# MEGA2560_Rev3e.net
KiCad netlist of a schematic drawn in EAGLE
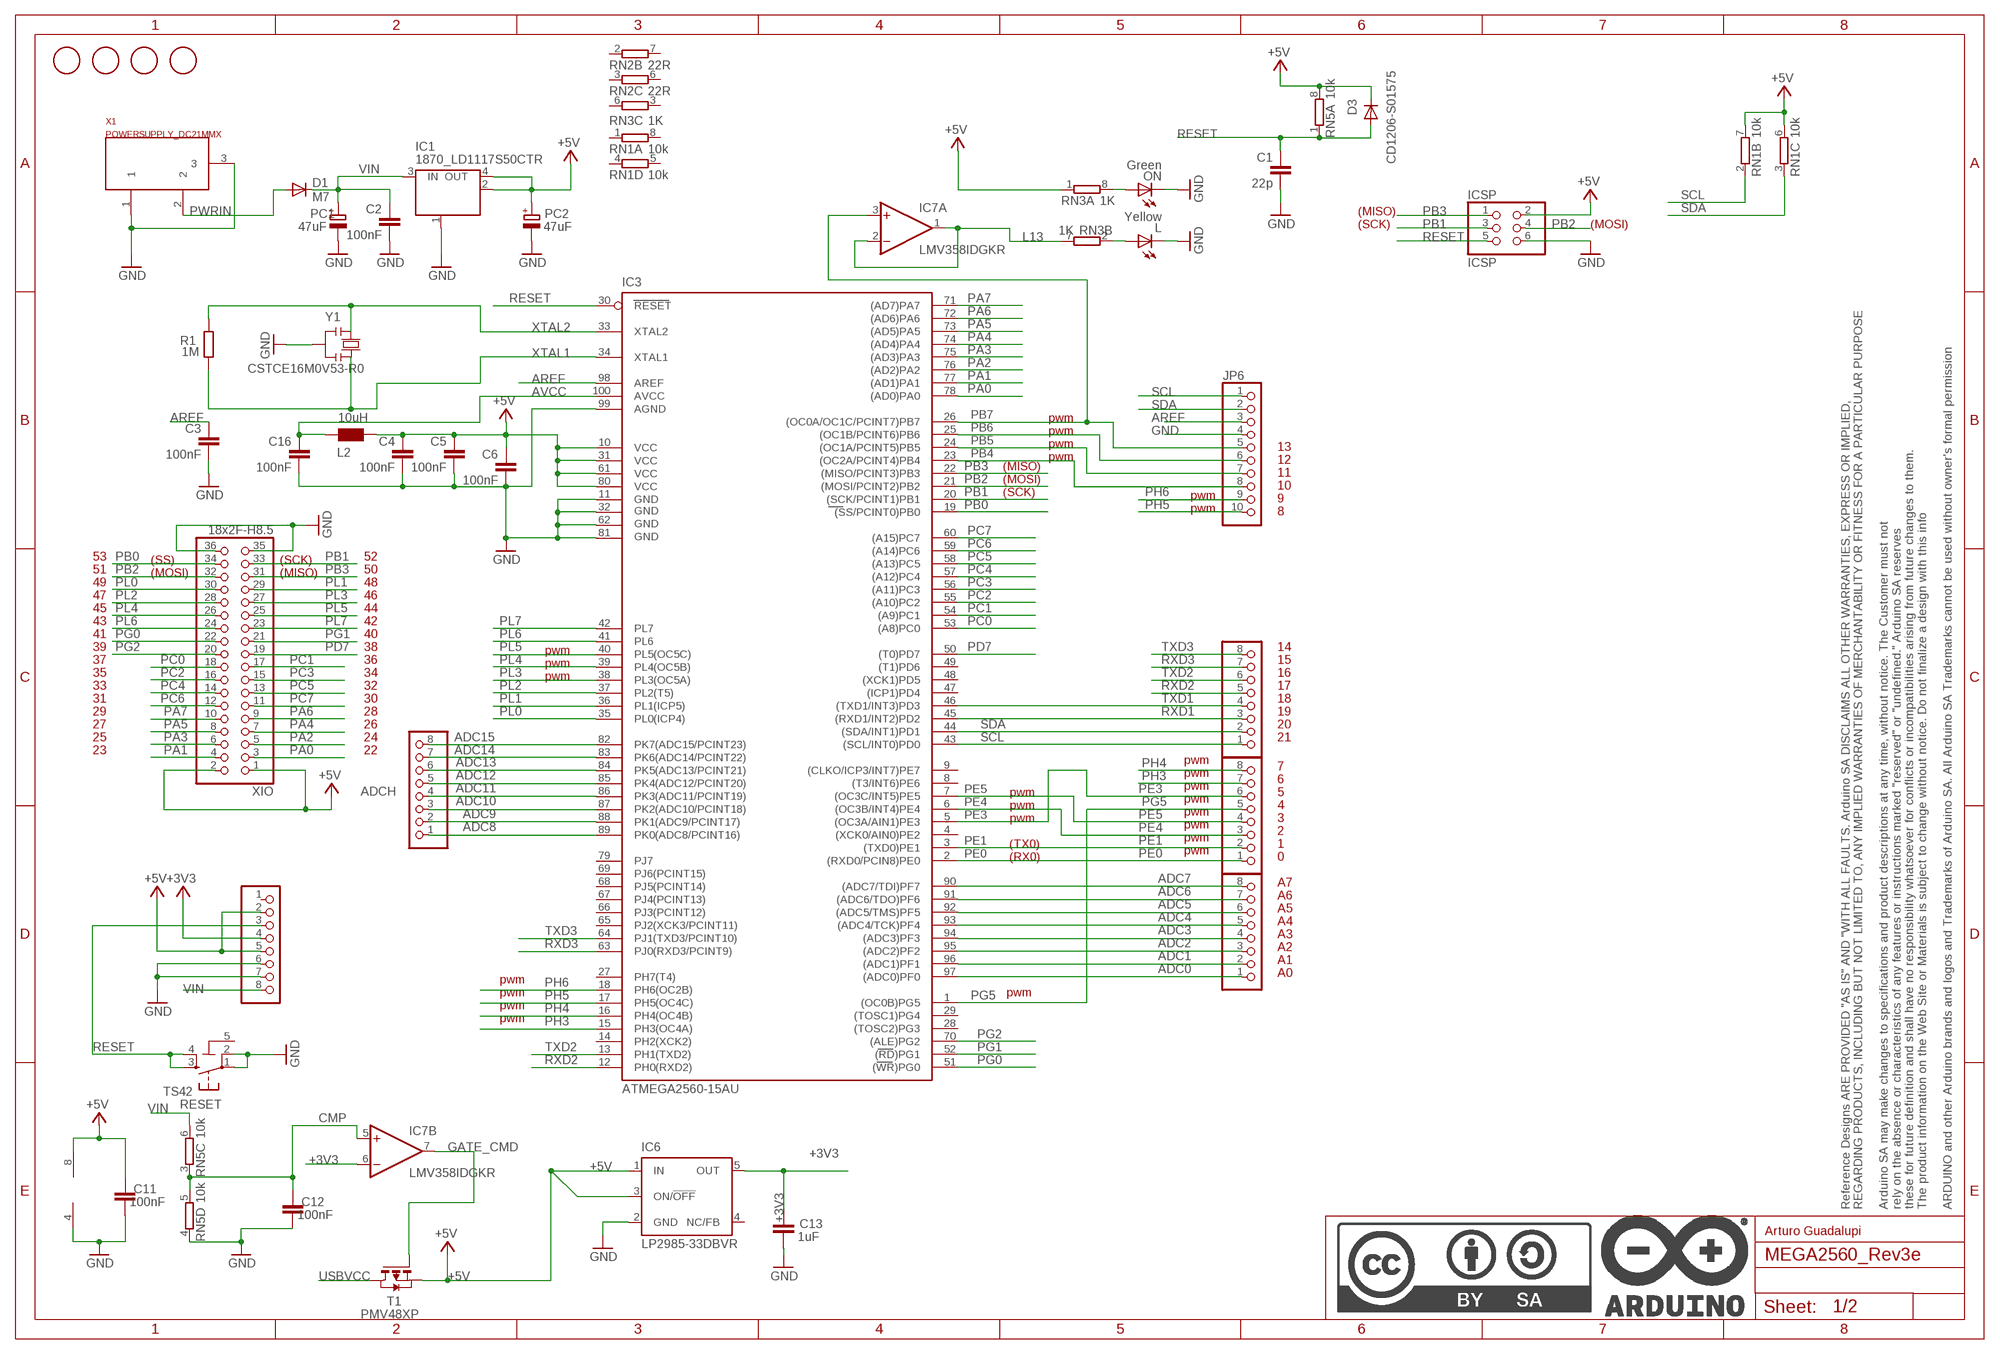
[diagram p0: schematic, sheet 1]
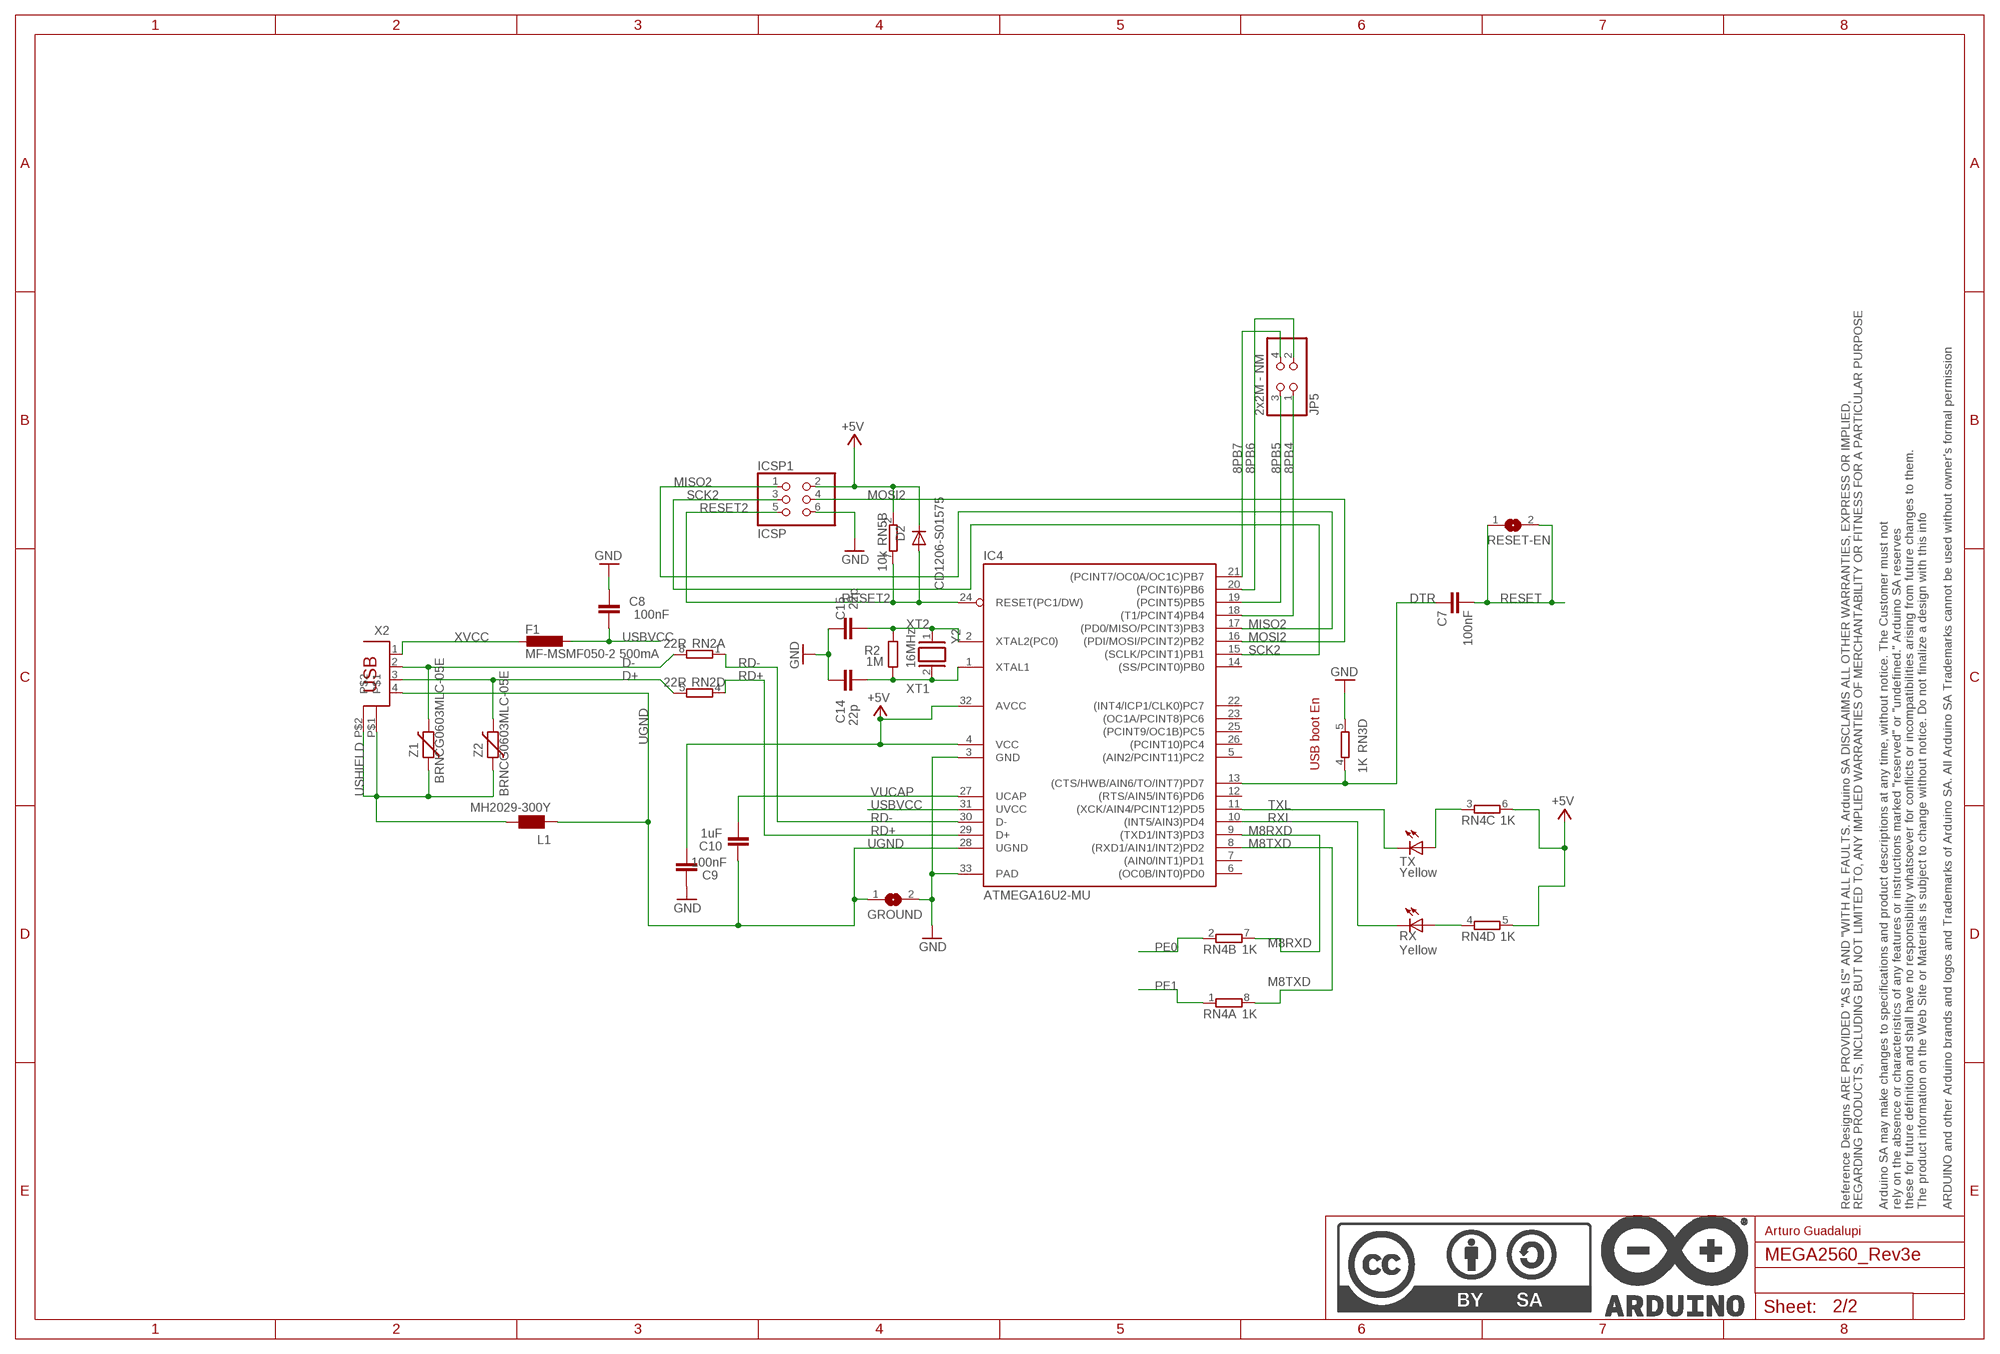
[diagram p1: schematic, sheet 2]

(export (version "E")
  (design (tool "Eeschema 10.0.6"))
  (components
    (comp (ref "C7")
      (value "100nF")
      (footprint "eagle-import:C0603-ROUND")
      (fields (field (name "PART_NUMBER") "cl10b104kbnc"))
      (libsource (lib "eagle-import") (part "0015_100NF_0603"))
    )
    (comp (ref "C8")
      (value "100nF")
      (footprint "eagle-import:C0603-ROUND")
      (fields (field (name "PART_NUMBER") "cl10b104kbnc"))
      (libsource (lib "eagle-import") (part "0015_100NF_0603"))
    )
    (comp (ref "C9")
      (value "100nF")
      (footprint "eagle-import:C0603-ROUND")
      (fields (field (name "PART_NUMBER") "cl10b104kbnc"))
      (libsource (lib "eagle-import") (part "0015_100NF_0603"))
    )
    (comp (ref "C10")
      (value "1uF")
      (footprint "eagle-import:C0603-ROUND")
      (fields (field (name "PART_NUMBER") "1uF_0603/GRM188R61E105KA12D"))
      (libsource (lib "eagle-import") (part "0006_1UF_0603/GRM188R61E105KA12D"))
    )
    (comp (ref "C14")
      (value "22p")
      (footprint "eagle-import:C0603-ROUND")
      (fields (field (name "PART_NUMBER") "22pF_0603"))
      (libsource (lib "eagle-import") (part "0014_22PF_0603"))
    )
    (comp (ref "C15")
      (value "22p")
      (footprint "eagle-import:C0603-ROUND")
      (fields (field (name "PART_NUMBER") "22pF_0603"))
      (libsource (lib "eagle-import") (part "0014_22PF_0603"))
    )
    (comp (ref "D2")
      (value "CD1206-S01575")
      (footprint "eagle-import:MINIMELF")
      (libsource (lib "eagle-import") (part "0012_CD1206-S01575"))
    )
    (comp (ref "F1")
      (value "MF-MSMF050-2 500mA")
      (footprint "eagle-import:L1812")
      (fields (field (name "PART_NUMBER") "MF-MSMF050-2"))
      (libsource (lib "eagle-import") (part "0002_MF-MSMF050-2"))
    )
    (comp (ref "GROUND")
      (value "SJ")
      (footprint "eagle-import:SJ")
      (libsource (lib "eagle-import") (part "SJ"))
    )
    (comp (ref "IC4")
      (value "ATMEGA16U2-MU")
      (footprint "eagle-import:MLF32")
      (fields (field (name "PART_NUMBER") "ATMEGA16U2-MUR"))
      (libsource (lib "eagle-import") (part "0007_ATMEGA16U2-MUR"))
    )
    (comp (ref "ICSP1")
      (value "ICSP")
      (footprint "eagle-import:2X03")
      (fields (field (name "PART_NUMBER") "PH254-203DF118A00V"))
      (libsource (lib "eagle-import") (part "0114_PH254-203DF118A00V"))
    )
    (comp (ref "JP5")
      (value "2x2M - NM")
      (footprint "eagle-import:2X02")
      (libsource (lib "eagle-import") (part "PINHD-2X2"))
    )
    (comp (ref "L1")
      (value "MH2029-300Y")
      (footprint "eagle-import:0805")
      (fields (field (name "PART_NUMBER") "BLM21PG300SN1D_/_MH2029-300Y"))
      (libsource (lib "eagle-import") (part "0001_BLM21PG300SN1D_/_MH2029-300Y"))
    )
    (comp (ref "R2")
      (value "1M")
      (footprint "eagle-import:R0603-ROUND")
      (fields (field (name "PART_NUMBER") "0603_1M"))
      (libsource (lib "eagle-import") (part "0004_0603_1M"))
    )
    (comp (ref "RESET-EN")
      (value "SJ")
      (footprint "eagle-import:SJ")
      (libsource (lib "eagle-import") (part "SJ"))
    )
    (comp (ref "RN2")
      (value "22R")
      (footprint "eagle-import:CAY16")
      (fields (field (name "PART_NUMBER") "064R_22R_/_CAY16-220J4LF"))
      (libsource (lib "eagle-import") (part "0003_064R_22R_/_CAY16-220J4LF"))
    )
    (comp (ref "RN3")
      (value "1K")
      (footprint "eagle-import:CAY16")
      (fields (field (name "PART_NUMBER") "064R_1K_/_CAY16-102J4LF"))
      (libsource (lib "eagle-import") (part "0005_064R_1K_/_CAY16-102J4LF"))
    )
    (comp (ref "RN4")
      (value "1K")
      (footprint "eagle-import:CAY16")
      (fields (field (name "PART_NUMBER") "064R_1K_/_CAY16-102J4LF"))
      (libsource (lib "eagle-import") (part "0005_064R_1K_/_CAY16-102J4LF"))
    )
    (comp (ref "RN5")
      (value "10k")
      (footprint "eagle-import:CAY16")
      (fields (field (name "PART_NUMBER") "064R_10K_/_CAY16-103J4LF"))
      (libsource (lib "eagle-import") (part "0016_064R_10K_/_CAY16-103J4LF"))
    )
    (comp (ref "RX")
      (value "Yellow")
      (footprint "eagle-import:CHIPLED_0805")
      (fields (field (name "PART_NUMBER") "KPT-2012YC"))
      (libsource (lib "eagle-import") (part "0044_KPT-2012YC"))
    )
    (comp (ref "TX")
      (value "Yellow")
      (footprint "eagle-import:CHIPLED_0805")
      (fields (field (name "PART_NUMBER") "KPT-2012YC"))
      (libsource (lib "eagle-import") (part "0044_KPT-2012YC"))
    )
    (comp (ref "U$2")
      (value "DNP")
      (footprint "eagle-import:FRAME")
      (libsource (lib "eagle-import") (part "A3-FRAME"))
    )
    (comp (ref "X2")
      (value "0056_USB-B-S-RA-WT-SPCC")
      (footprint "eagle-import:PN61729")
      (fields (field (name "PART_NUMBER") "USB-B-S-RA-WT-SPCC"))
      (libsource (lib "eagle-import") (part "0056_USB-B-S-RA-WT-SPCC"))
    )
    (comp (ref "Y2")
      (value "16MHz")
      (footprint "eagle-import:QS")
      (fields (field (name "PART_NUMBER") "P011052006 16M/FTX16M20S"))
      (libsource (lib "eagle-import") (part "0019_P011052006_16M"))
    )
    (comp (ref "Z1")
      (value "BRNCG0603MLC-05E")
      (footprint "eagle-import:CT_CN0603")
      (libsource (lib "eagle-import") (part "0010_BRNCG0603MLC-05E"))
    )
    (comp (ref "Z2")
      (value "BRNCG0603MLC-05E")
      (footprint "eagle-import:CT_CN0603")
      (libsource (lib "eagle-import") (part "0010_BRNCG0603MLC-05E"))
    )
    (comp (ref "ADCH")
      (value "FH254-108DF08500V")
      (footprint "eagle-import:1X08")
      (libsource (lib "eagle-import") (part "0058_FH254-108DF08500V"))
    )
    (comp (ref "ADCL")
      (value "FH254-108DF08500V")
      (footprint "eagle-import:1X08")
      (libsource (lib "eagle-import") (part "0058_FH254-108DF08500V"))
    )
    (comp (ref "C1")
      (value "22p")
      (footprint "eagle-import:C0603-ROUND")
      (fields (field (name "PART_NUMBER") "22pF_0603"))
      (libsource (lib "eagle-import") (part "0014_22PF_0603"))
    )
    (comp (ref "C2")
      (value "100nF")
      (footprint "eagle-import:C0603-ROUND")
      (fields (field (name "PART_NUMBER") "cl10b104kbnc"))
      (libsource (lib "eagle-import") (part "0015_100NF_0603"))
    )
    (comp (ref "C3")
      (value "100nF")
      (footprint "eagle-import:C0603-ROUND")
      (fields (field (name "PART_NUMBER") "cl10b104kbnc"))
      (libsource (lib "eagle-import") (part "0015_100NF_0603"))
    )
    (comp (ref "C4")
      (value "100nF")
      (footprint "eagle-import:C0603-ROUND")
      (fields (field (name "PART_NUMBER") "cl10b104kbnc"))
      (libsource (lib "eagle-import") (part "0015_100NF_0603"))
    )
    (comp (ref "C5")
      (value "100nF")
      (footprint "eagle-import:C0603-ROUND")
      (fields (field (name "PART_NUMBER") "cl10b104kbnc"))
      (libsource (lib "eagle-import") (part "0015_100NF_0603"))
    )
    (comp (ref "C6")
      (value "100nF")
      (footprint "eagle-import:C0603-ROUND")
      (fields (field (name "PART_NUMBER") "cl10b104kbnc"))
      (libsource (lib "eagle-import") (part "0015_100NF_0603"))
    )
    (comp (ref "C11")
      (value "100nF")
      (footprint "eagle-import:C0603-ROUND")
      (fields (field (name "PART_NUMBER") "cl10b104kbnc"))
      (libsource (lib "eagle-import") (part "0015_100NF_0603"))
    )
    (comp (ref "C12")
      (value "100nF")
      (footprint "eagle-import:C0603-ROUND")
      (fields (field (name "PART_NUMBER") "cl10b104kbnc"))
      (libsource (lib "eagle-import") (part "0015_100NF_0603"))
    )
    (comp (ref "C13")
      (value "1uF")
      (footprint "eagle-import:C0603-ROUND")
      (fields (field (name "PART_NUMBER") "1uF_0603/GRM188R61E105KA12D"))
      (libsource (lib "eagle-import") (part "0006_1UF_0603/GRM188R61E105KA12D"))
    )
    (comp (ref "C16")
      (value "100nF")
      (footprint "eagle-import:C0603-ROUND")
      (fields (field (name "PART_NUMBER") "cl10b104kbnc"))
      (libsource (lib "eagle-import") (part "0015_100NF_0603"))
    )
    (comp (ref "COMMUNICATION")
      (value "FH254-108DF08500V")
      (footprint "eagle-import:1X08")
      (libsource (lib "eagle-import") (part "0058_FH254-108DF08500V"))
    )
    (comp (ref "D1")
      (value "M7")
      (footprint "eagle-import:SMB")
      (libsource (lib "eagle-import") (part "0020_M7"))
    )
    (comp (ref "D3")
      (value "CD1206-S01575")
      (footprint "eagle-import:MINIMELF")
      (libsource (lib "eagle-import") (part "0012_CD1206-S01575"))
    )
    (comp (ref "FD1")
      (value "FIDUCIALMOUNT")
      (footprint "eagle-import:FIDUCIA-MOUNT")
      (libsource (lib "eagle-import") (part "FIDUCIALMOUNT"))
    )
    (comp (ref "FD2")
      (value "FIDUCIALMOUNT")
      (footprint "eagle-import:FIDUCIA-MOUNT")
      (libsource (lib "eagle-import") (part "FIDUCIALMOUNT"))
    )
    (comp (ref "FD3")
      (value "FIDUCIALMOUNT")
      (footprint "eagle-import:FIDUCIA-MOUNT")
      (libsource (lib "eagle-import") (part "FIDUCIALMOUNT"))
    )
    (comp (ref "FD4")
      (value "FIDUCIALMOUNT")
      (footprint "eagle-import:FIDUCIA-MOUNT")
      (libsource (lib "eagle-import") (part "FIDUCIALMOUNT"))
    )
    (comp (ref "IC1")
      (value "1870_LD1117S50CTR")
      (footprint "eagle-import:LINEAR_SOT223")
      (fields (field (name "PART_NUMBER") "LD1117S50CTR"))
      (libsource (lib "eagle-import") (part "1870_LD1117S50CTR"))
    )
    (comp (ref "IC3")
      (value "ATMEGA2560-15AU")
      (footprint "eagle-import:TQFP100")
      (fields (field (name "PART_NUMBER") "ATMEGA2560-16AU"))
      (libsource (lib "eagle-import") (part "0023_ATMEGA2560-16AU"))
    )
    (comp (ref "IC6")
      (value "LP2985-33DBVR")
      (footprint "eagle-import:SOT23-DBV")
      (fields (field (name "PART_NUMBER") "TEXLP2985-33DBVR"))
      (libsource (lib "eagle-import") (part "0008_TEXLP2985-33DBVR"))
    )
    (comp (ref "IC7")
      (value "LMV358IDGKR")
      (footprint "eagle-import:MSOP08")
      (libsource (lib "eagle-import") (part "0021_LMV358IDGKR"))
    )
    (comp (ref "ICSP")
      (value "ICSP")
      (footprint "eagle-import:2X03")
      (fields (field (name "PART_NUMBER") "PH254-203DF118A00V"))
      (libsource (lib "eagle-import") (part "0114_PH254-203DF118A00V"))
    )
    (comp (ref "JP6")
      (value "FH254-110DF08500V")
      (footprint "eagle-import:1X10")
      (fields (field (name "PART_NUMBER") "FH254-110DF08500T30"))
      (libsource (lib "eagle-import") (part "1216_FH254-110DF08500T30"))
    )
    (comp (ref "L")
      (value "Yellow")
      (footprint "eagle-import:CHIPLED_0805")
      (fields (field (name "PART_NUMBER") "KPT-2012YC"))
      (libsource (lib "eagle-import") (part "0044_KPT-2012YC"))
    )
    (comp (ref "L2")
      (value "10uH")
      (footprint "eagle-import:0805")
      (fields (field (name "PART_NUMBER") "CV201210-100K"))
      (libsource (lib "eagle-import") (part "0715_CV201210-100K"))
    )
    (comp (ref "ON")
      (value "Green")
      (footprint "eagle-import:CHIPLED_0805")
      (fields (field (name "PART_NUMBER") "KPT-2012SGC"))
      (libsource (lib "eagle-import") (part "0043_KPT-2012SGC"))
    )
    (comp (ref "PC1")
      (value "47uF")
      (footprint "eagle-import:PANASONIC_D")
      (libsource (lib "eagle-import") (part "0113_47UF"))
    )
    (comp (ref "PC2")
      (value "47uF")
      (footprint "eagle-import:PANASONIC_D")
      (libsource (lib "eagle-import") (part "0113_47UF"))
    )
    (comp (ref "POWER")
      (value "FH254-108DF08500V")
      (footprint "eagle-import:1X08")
      (fields (field (name "PART_NUMBER") "FH254-108DF08500T21"))
      (libsource (lib "eagle-import") (part "1217_FH254-108DF08500T21"))
    )
    (comp (ref "PWML")
      (value "FH254-108DF08500V")
      (footprint "eagle-import:1X08")
      (fields (field (name "PART_NUMBER") "FH254-108DF08500T20"))
      (libsource (lib "eagle-import") (part "1218_FH254-108DF08500T20"))
    )
    (comp (ref "R1")
      (value "1M")
      (footprint "eagle-import:R0603-ROUND")
      (fields (field (name "PART_NUMBER") "0603_1M"))
      (libsource (lib "eagle-import") (part "0004_0603_1M"))
    )
    (comp (ref "RESET")
      (value "TS42")
      (footprint "eagle-import:TS42")
      (fields (field (name "PART_NUMBER") "IT-1157AHNP-160G-G_GTR"))
      (libsource (lib "eagle-import") (part "0946_TS42031-160W-TR-7260"))
    )
    (comp (ref "RN1")
      (value "10k")
      (footprint "eagle-import:CAY16")
      (fields (field (name "PART_NUMBER") "064R_10K_/_CAY16-103J4LF"))
      (libsource (lib "eagle-import") (part "0016_064R_10K_/_CAY16-103J4LF"))
    )
    (comp (ref "T1")
      (value "PMV48XP")
      (footprint "eagle-import:SOT-23")
      (fields (field (name "CASE") "SOT23") (field (name "PART_NUMBER") "PMV48XP"))
      (libsource (lib "eagle-import") (part "0297_PMV48XP"))
    )
    (comp (ref "U$1")
      (value "DNP")
      (footprint "eagle-import:FRAME")
      (libsource (lib "eagle-import") (part "A3-FRAME"))
    )
    (comp (ref "X1")
      (value "POWERSUPPLY_DC21MMX")
      (footprint "eagle-import:POWERSUPPLY_DC-21MM")
      (libsource (lib "eagle-import") (part "POWERSUPPLY_DC21MMX"))
    )
    (comp (ref "XIO")
      (value "18x2F-H8.5")
      (footprint "eagle-import:2X18")
      (fields (field (name "PART_NUMBER") "FH254-218DF08500V"))
      (libsource (lib "eagle-import") (part "0060_FH254-218DF08500V"))
    )
    (comp (ref "Y1")
      (value "CSTCE16M0V53-R0")
      (footprint "eagle-import:RESONATOR")
      (libsource (lib "eagle-import") (part "0011_CSTCE16M0V53-R0"))
    )
  )
  (nets
    (net (code "1") (name "+3V3") (class "Default")
      (node (ref "C13") (pin "2") (pinfunction "2_2") (pintype "passive"))
      (node (ref "IC6") (pin "5") (pinfunction "OUT_5") (pintype "passive"))
      (node (ref "IC7") (pin "6") (pinfunction "-IN_6") (pintype "input"))
      (node (ref "POWER") (pin "4") (pinfunction "4_4") (pintype "passive"))
    )
    (net (code "2") (name "+5V") (class "Default")
      (node (ref "C11") (pin "2") (pinfunction "2_2") (pintype "passive"))
      (node (ref "C4") (pin "1") (pinfunction "1_1") (pintype "passive"))
      (node (ref "C5") (pin "1") (pinfunction "1_1") (pintype "passive"))
      (node (ref "C6") (pin "1") (pinfunction "1_1") (pintype "passive"))
      (node (ref "C9") (pin "1") (pinfunction "1_1") (pintype "passive"))
      (node (ref "D2") (pin "C") (pinfunction "C_C") (pintype "passive"))
      (node (ref "D3") (pin "C") (pinfunction "C_C") (pintype "passive"))
      (node (ref "IC1") (pin "2") (pinfunction "OUT_2") (pintype "passive"))
      (node (ref "IC1") (pin "4") (pinfunction "OUT_4") (pintype "passive"))
      (node (ref "IC3") (pin "10") (pinfunction "VCC_10") (pintype "power_in"))
      (node (ref "IC3") (pin "31") (pinfunction "VCC1_31") (pintype "power_in"))
      (node (ref "IC3") (pin "61") (pinfunction "VCC2_61") (pintype "power_in"))
      (node (ref "IC3") (pin "80") (pinfunction "VCC3_80") (pintype "power_in"))
      (node (ref "IC4") (pin "32") (pinfunction "AVCC_32") (pintype "power_in"))
      (node (ref "IC4") (pin "4") (pinfunction "VCC_4") (pintype "power_in"))
      (node (ref "IC6") (pin "1") (pinfunction "IN_1") (pintype "input"))
      (node (ref "IC6") (pin "3") (pinfunction "ON/~{OFF}_3") (pintype "input"))
      (node (ref "IC7") (pin "8") (pinfunction "V+_8") (pintype "power_in"))
      (node (ref "ICSP") (pin "2") (pinfunction "2_2") (pintype "passive"))
      (node (ref "ICSP1") (pin "2") (pinfunction "2_2") (pintype "passive"))
      (node (ref "L2") (pin "2") (pinfunction "2_2") (pintype "passive"))
      (node (ref "PC2") (pin "+") (pinfunction "+_+") (pintype "passive"))
      (node (ref "POWER") (pin "2") (pinfunction "2_2") (pintype "passive"))
      (node (ref "POWER") (pin "5") (pinfunction "5_5") (pintype "passive"))
      (node (ref "RN1") (pin "6") (pinfunction "2_6") (pintype "passive"))
      (node (ref "RN1") (pin "7") (pinfunction "2_7") (pintype "passive"))
      (node (ref "RN3") (pin "1") (pinfunction "1_1") (pintype "passive"))
      (node (ref "RN4") (pin "5") (pinfunction "2_5") (pintype "passive"))
      (node (ref "RN4") (pin "6") (pinfunction "2_6") (pintype "passive"))
      (node (ref "RN5") (pin "2") (pinfunction "1_2") (pintype "passive"))
      (node (ref "RN5") (pin "8") (pinfunction "2_8") (pintype "passive"))
      (node (ref "T1") (pin "2") (pinfunction "S_2") (pintype "passive"))
      (node (ref "XIO") (pin "1") (pinfunction "1_1") (pintype "passive"))
      (node (ref "XIO") (pin "2") (pinfunction "2_2") (pintype "passive"))
    )
    (net (code "3") (name "5-GND") (class "Default")
      (node (ref "RESET") (pin "5") (pinfunction "5-GND_5") (pintype "power_in"))
    )
    (net (code "4") (name "8PB4") (class "Default")
      (node (ref "IC4") (pin "18") (pinfunction "(T1/PCINT4)PB4_18") (pintype "bidirectional"))
      (node (ref "JP5") (pin "1") (pinfunction "1_1") (pintype "passive"))
    )
    (net (code "5") (name "8PB5") (class "Default")
      (node (ref "IC4") (pin "19") (pinfunction "(PCINT5)PB5_19") (pintype "bidirectional"))
      (node (ref "JP5") (pin "3") (pinfunction "3_3") (pintype "passive"))
    )
    (net (code "6") (name "8PB6") (class "Default")
      (node (ref "IC4") (pin "20") (pinfunction "(PCINT6)PB6_20") (pintype "bidirectional"))
      (node (ref "JP5") (pin "2") (pinfunction "2_2") (pintype "passive"))
    )
    (net (code "7") (name "8PB7") (class "Default")
      (node (ref "IC4") (pin "21") (pinfunction "(PCINT7/OC0A/OC1C)PB7_21") (pintype "bidirectional"))
      (node (ref "JP5") (pin "4") (pinfunction "4_4") (pintype "passive"))
    )
    (net (code "8") (name "ADC0") (class "Default")
      (node (ref "ADCL") (pin "1") (pinfunction "1_1") (pintype "passive"))
      (node (ref "IC3") (pin "97") (pinfunction "(ADC0)PF0_97") (pintype "bidirectional"))
    )
    (net (code "9") (name "ADC1") (class "Default")
      (node (ref "ADCL") (pin "2") (pinfunction "2_2") (pintype "passive"))
      (node (ref "IC3") (pin "96") (pinfunction "(ADC1)PF1_96") (pintype "bidirectional"))
    )
    (net (code "10") (name "ADC2") (class "Default")
      (node (ref "ADCL") (pin "3") (pinfunction "3_3") (pintype "passive"))
      (node (ref "IC3") (pin "95") (pinfunction "(ADC2)PF2_95") (pintype "bidirectional"))
    )
    (net (code "11") (name "ADC3") (class "Default")
      (node (ref "ADCL") (pin "4") (pinfunction "4_4") (pintype "passive"))
      (node (ref "IC3") (pin "94") (pinfunction "(ADC3)PF3_94") (pintype "bidirectional"))
    )
    (net (code "12") (name "ADC4") (class "Default")
      (node (ref "ADCL") (pin "5") (pinfunction "5_5") (pintype "passive"))
      (node (ref "IC3") (pin "93") (pinfunction "(ADC4/TCK)PF4_93") (pintype "bidirectional"))
    )
    (net (code "13") (name "ADC5") (class "Default")
      (node (ref "ADCL") (pin "6") (pinfunction "6_6") (pintype "passive"))
      (node (ref "IC3") (pin "92") (pinfunction "(ADC5/TMS)PF5_92") (pintype "bidirectional"))
    )
    (net (code "14") (name "ADC6") (class "Default")
      (node (ref "ADCL") (pin "7") (pinfunction "7_7") (pintype "passive"))
      (node (ref "IC3") (pin "91") (pinfunction "(ADC6/TDO)PF6_91") (pintype "bidirectional"))
    )
    (net (code "15") (name "ADC7") (class "Default")
      (node (ref "ADCL") (pin "8") (pinfunction "8_8") (pintype "passive"))
      (node (ref "IC3") (pin "90") (pinfunction "(ADC7/TDI)PF7_90") (pintype "bidirectional"))
    )
    (net (code "16") (name "ADC8") (class "Default")
      (node (ref "ADCH") (pin "1") (pinfunction "1_1") (pintype "passive"))
      (node (ref "IC3") (pin "89") (pinfunction "PK0(ADC8/PCINT16)_89") (pintype "bidirectional"))
    )
    (net (code "17") (name "ADC9") (class "Default")
      (node (ref "ADCH") (pin "2") (pinfunction "2_2") (pintype "passive"))
      (node (ref "IC3") (pin "88") (pinfunction "PK1(ADC9/PCINT17)_88") (pintype "bidirectional"))
    )
    (net (code "18") (name "ADC10") (class "Default")
      (node (ref "ADCH") (pin "3") (pinfunction "3_3") (pintype "passive"))
      (node (ref "IC3") (pin "87") (pinfunction "PK2(ADC10/PCINT18)_87") (pintype "bidirectional"))
    )
    (net (code "19") (name "ADC11") (class "Default")
      (node (ref "ADCH") (pin "4") (pinfunction "4_4") (pintype "passive"))
      (node (ref "IC3") (pin "86") (pinfunction "PK3(ADC11/PCINT19)_86") (pintype "bidirectional"))
    )
    (net (code "20") (name "ADC12") (class "Default")
      (node (ref "ADCH") (pin "5") (pinfunction "5_5") (pintype "passive"))
      (node (ref "IC3") (pin "85") (pinfunction "PK4(ADC12/PCINT20)_85") (pintype "bidirectional"))
    )
    (net (code "21") (name "ADC13") (class "Default")
      (node (ref "ADCH") (pin "6") (pinfunction "6_6") (pintype "passive"))
      (node (ref "IC3") (pin "84") (pinfunction "PK5(ADC13/PCINT21)_84") (pintype "bidirectional"))
    )
    (net (code "22") (name "ADC14") (class "Default")
      (node (ref "ADCH") (pin "7") (pinfunction "7_7") (pintype "passive"))
      (node (ref "IC3") (pin "83") (pinfunction "PK6(ADC14/PCINT22)_83") (pintype "bidirectional"))
    )
    (net (code "23") (name "ADC15") (class "Default")
      (node (ref "ADCH") (pin "8") (pinfunction "8_8") (pintype "passive"))
      (node (ref "IC3") (pin "82") (pinfunction "PK7(ADC15/PCINT23)_82") (pintype "bidirectional"))
    )
    (net (code "24") (name "AREF") (class "Default")
      (node (ref "C3") (pin "1") (pinfunction "1_1") (pintype "passive"))
      (node (ref "IC3") (pin "98") (pinfunction "AREF_98") (pintype "bidirectional"))
      (node (ref "JP6") (pin "3") (pinfunction "3_3") (pintype "passive"))
    )
    (net (code "25") (name "AVCC") (class "Default")
      (node (ref "C16") (pin "1") (pinfunction "1_1") (pintype "passive"))
      (node (ref "IC3") (pin "100") (pinfunction "AVCC_100") (pintype "power_in"))
      (node (ref "L2") (pin "1") (pinfunction "1_1") (pintype "passive"))
    )
    (net (code "26") (name "CMP") (class "Default")
      (node (ref "C12") (pin "2") (pinfunction "2_2") (pintype "passive"))
      (node (ref "IC7") (pin "5") (pinfunction "+IN_5") (pintype "input"))
      (node (ref "RN5") (pin "3") (pinfunction "1_3") (pintype "passive"))
      (node (ref "RN5") (pin "5") (pinfunction "2_5") (pintype "passive"))
    )
    (net (code "27") (name "D+") (class "Default")
      (node (ref "RN2") (pin "5") (pinfunction "2_5") (pintype "passive"))
      (node (ref "X2") (pin "3") (pinfunction "3_3") (pintype "bidirectional"))
      (node (ref "Z2") (pin "2") (pinfunction "2_2") (pintype "passive"))
    )
    (net (code "28") (name "D-") (class "Default")
      (node (ref "RN2") (pin "8") (pinfunction "2_8") (pintype "passive"))
      (node (ref "X2") (pin "2") (pinfunction "2_2") (pintype "bidirectional"))
      (node (ref "Z1") (pin "2") (pinfunction "2_2") (pintype "passive"))
    )
    (net (code "29") (name "DTR") (class "Default")
      (node (ref "C7") (pin "1") (pinfunction "1_1") (pintype "passive"))
      (node (ref "IC4") (pin "13") (pinfunction "(CTS/HWB/AIN6/TO/INT7)PD7_13") (pintype "bidirectional"))
      (node (ref "RN3") (pin "4") (pinfunction "1_4") (pintype "passive"))
    )
    (net (code "30") (name "GATE_CMD") (class "Default")
      (node (ref "IC7") (pin "7") (pinfunction "OUT_7") (pintype "output"))
      (node (ref "T1") (pin "3") (pinfunction "G_3") (pintype "passive"))
    )
    (net (code "31") (name "GND") (class "Default")
      (node (ref "C1") (pin "2") (pinfunction "2_2") (pintype "passive"))
      (node (ref "C11") (pin "1") (pinfunction "1_1") (pintype "passive"))
      (node (ref "C12") (pin "1") (pinfunction "1_1") (pintype "passive"))
      (node (ref "C13") (pin "1") (pinfunction "1_1") (pintype "passive"))
      (node (ref "C14") (pin "2") (pinfunction "2_2") (pintype "passive"))
      (node (ref "C15") (pin "2") (pinfunction "2_2") (pintype "passive"))
      (node (ref "C16") (pin "2") (pinfunction "2_2") (pintype "passive"))
      (node (ref "C2") (pin "2") (pinfunction "2_2") (pintype "passive"))
      (node (ref "C3") (pin "2") (pinfunction "2_2") (pintype "passive"))
      (node (ref "C4") (pin "2") (pinfunction "2_2") (pintype "passive"))
      (node (ref "C5") (pin "2") (pinfunction "2_2") (pintype "passive"))
      (node (ref "C6") (pin "2") (pinfunction "2_2") (pintype "passive"))
      (node (ref "C8") (pin "2") (pinfunction "2_2") (pintype "passive"))
      (node (ref "C9") (pin "2") (pinfunction "2_2") (pintype "passive"))
      (node (ref "GROUND") (pin "2") (pinfunction "2_2") (pintype "passive"))
      (node (ref "IC1") (pin "1") (pinfunction "GND/ADJ_1") (pintype "input"))
      (node (ref "IC3") (pin "11") (pinfunction "GND_11") (pintype "power_in"))
      (node (ref "IC3") (pin "32") (pinfunction "GND1_32") (pintype "power_in"))
      (node (ref "IC3") (pin "62") (pinfunction "GND2_62") (pintype "power_in"))
      (node (ref "IC3") (pin "81") (pinfunction "GND3_81") (pintype "power_in"))
      (node (ref "IC3") (pin "99") (pinfunction "AGND_99") (pintype "power_in"))
      (node (ref "IC4") (pin "3") (pinfunction "GND_3") (pintype "power_in"))
      (node (ref "IC4") (pin "33") (pinfunction "PAD_33") (pintype "power_in"))
      (node (ref "IC6") (pin "2") (pinfunction "GND_2") (pintype "power_in"))
      (node (ref "IC7") (pin "4") (pinfunction "V-_4") (pintype "power_in"))
      (node (ref "ICSP") (pin "6") (pinfunction "6_6") (pintype "passive"))
      (node (ref "ICSP1") (pin "6") (pinfunction "6_6") (pintype "passive"))
      (node (ref "JP6") (pin "4") (pinfunction "4_4") (pintype "passive"))
      (node (ref "L") (pin "C") (pinfunction "C_C") (pintype "passive"))
      (node (ref "ON") (pin "C") (pinfunction "C_C") (pintype "passive"))
      (node (ref "PC1") (pin "-") (pinfunction "-_-") (pintype "passive"))
      (node (ref "PC2") (pin "-") (pinfunction "-_-") (pintype "passive"))
      (node (ref "POWER") (pin "6") (pinfunction "6_6") (pintype "passive"))
      (node (ref "POWER") (pin "7") (pinfunction "7_7") (pintype "passive"))
      (node (ref "RESET") (pin "1") (pinfunction "1_1") (pintype "passive"))
      (node (ref "RESET") (pin "2") (pinfunction "2_2") (pintype "passive"))
      (node (ref "RN3") (pin "5") (pinfunction "2_5") (pintype "passive"))
      (node (ref "RN5") (pin "4") (pinfunction "1_4") (pintype "passive"))
      (node (ref "X1") (pin "1") (pinfunction "1_1") (pintype "power_in"))
      (node (ref "X1") (pin "3") (pinfunction "3_3") (pintype "power_in"))
      (node (ref "XIO") (pin "35") (pinfunction "35_35") (pintype "passive"))
      (node (ref "XIO") (pin "36") (pinfunction "36_36") (pintype "passive"))
      (node (ref "Y1") (pin "2") (pinfunction "2_2") (pintype "passive"))
    )
    (net (code "32") (name "L13") (class "Default")
      (node (ref "IC7") (pin "1") (pinfunction "OUT_1") (pintype "output"))
      (node (ref "IC7") (pin "2") (pinfunction "-IN_2") (pintype "input"))
      (node (ref "RN3") (pin "7") (pinfunction "2_7") (pintype "passive"))
    )
    (net (code "33") (name "M8RXD") (class "Default")
      (node (ref "IC4") (pin "9") (pinfunction "(TXD1/INT3)PD3_9") (pintype "bidirectional"))
      (node (ref "RN4") (pin "7") (pinfunction "2_7") (pintype "passive"))
    )
    (net (code "34") (name "M8TXD") (class "Default")
      (node (ref "IC4") (pin "8") (pinfunction "(RXD1/AIN1/INT2)PD2_8") (pintype "bidirectional"))
      (node (ref "RN4") (pin "8") (pinfunction "2_8") (pintype "passive"))
    )
    (net (code "35") (name "MISO2") (class "Default")
      (node (ref "IC4") (pin "17") (pinfunction "(PD0/MISO/PCINT3)PB3_17") (pintype "bidirectional"))
      (node (ref "ICSP1") (pin "1") (pinfunction "1_1") (pintype "passive"))
    )
    (net (code "36") (name "MOSI2") (class "Default")
      (node (ref "IC4") (pin "16") (pinfunction "(PDI/MOSI/PCINT2)PB2_16") (pintype "bidirectional"))
      (node (ref "ICSP1") (pin "4") (pinfunction "4_4") (pintype "passive"))
    )
    (net (code "37") (name "Net-(RN3A-2)") (class "Default")
      (node (ref "ON") (pin "A") (pinfunction "A_A") (pintype "passive"))
      (node (ref "RN3") (pin "8") (pinfunction "2_8") (pintype "passive"))
    )
    (net (code "38") (name "Net-(RN3B-1)") (class "Default")
      (node (ref "L") (pin "A") (pinfunction "A_A") (pintype "passive"))
      (node (ref "RN3") (pin "2") (pinfunction "1_2") (pintype "passive"))
    )
    (net (code "39") (name "Net-(RN4C-1)") (class "Default")
      (node (ref "RN4") (pin "3") (pinfunction "1_3") (pintype "passive"))
      (node (ref "TX") (pin "A") (pinfunction "A_A") (pintype "passive"))
    )
    (net (code "40") (name "Net-(RN4D-1)") (class "Default")
      (node (ref "RN4") (pin "4") (pinfunction "1_4") (pintype "passive"))
      (node (ref "RX") (pin "A") (pinfunction "A_A") (pintype "passive"))
    )
    (net (code "41") (name "PA0") (class "Default")
      (node (ref "IC3") (pin "78") (pinfunction "(AD0)PA0_78") (pintype "bidirectional"))
      (node (ref "XIO") (pin "3") (pinfunction "3_3") (pintype "passive"))
    )
    (net (code "42") (name "PA1") (class "Default")
      (node (ref "IC3") (pin "77") (pinfunction "(AD1)PA1_77") (pintype "bidirectional"))
      (node (ref "XIO") (pin "4") (pinfunction "4_4") (pintype "passive"))
    )
    (net (code "43") (name "PA2") (class "Default")
      (node (ref "IC3") (pin "76") (pinfunction "(AD2)PA2_76") (pintype "bidirectional"))
      (node (ref "XIO") (pin "5") (pinfunction "5_5") (pintype "passive"))
    )
    (net (code "44") (name "PA3") (class "Default")
      (node (ref "IC3") (pin "75") (pinfunction "(AD3)PA3_75") (pintype "bidirectional"))
      (node (ref "XIO") (pin "6") (pinfunction "6_6") (pintype "passive"))
    )
    (net (code "45") (name "PA4") (class "Default")
      (node (ref "IC3") (pin "74") (pinfunction "(AD4)PA4_74") (pintype "bidirectional"))
      (node (ref "XIO") (pin "7") (pinfunction "7_7") (pintype "passive"))
    )
    (net (code "46") (name "PA5") (class "Default")
      (node (ref "IC3") (pin "73") (pinfunction "(AD5)PA5_73") (pintype "bidirectional"))
      (node (ref "XIO") (pin "8") (pinfunction "8_8") (pintype "passive"))
    )
    (net (code "47") (name "PA6") (class "Default")
      (node (ref "IC3") (pin "72") (pinfunction "(AD6)PA6_72") (pintype "bidirectional"))
      (node (ref "XIO") (pin "9") (pinfunction "9_9") (pintype "passive"))
    )
    (net (code "48") (name "PA7") (class "Default")
      (node (ref "IC3") (pin "71") (pinfunction "(AD7)PA7_71") (pintype "bidirectional"))
      (node (ref "XIO") (pin "10") (pinfunction "10_10") (pintype "passive"))
    )
    (net (code "49") (name "PB0") (class "Default")
      (node (ref "IC3") (pin "19") (pinfunction "(SS/PCINT0)PB0_19") (pintype "bidirectional"))
      (node (ref "XIO") (pin "34") (pinfunction "34_34") (pintype "passive"))
    )
    (net (code "50") (name "PB1") (class "Default")
      (node (ref "IC3") (pin "20") (pinfunction "(SCK/PCINT1)PB1_20") (pintype "bidirectional"))
      (node (ref "ICSP") (pin "3") (pinfunction "3_3") (pintype "passive"))
      (node (ref "XIO") (pin "33") (pinfunction "33_33") (pintype "passive"))
    )
    (net (code "51") (name "PB2") (class "Default")
      (node (ref "IC3") (pin "21") (pinfunction "(MOSI/PCINT2)PB2_21") (pintype "bidirectional"))
      (node (ref "ICSP") (pin "4") (pinfunction "4_4") (pintype "passive"))
      (node (ref "XIO") (pin "32") (pinfunction "32_32") (pintype "passive"))
    )
    (net (code "52") (name "PB3") (class "Default")
      (node (ref "IC3") (pin "22") (pinfunction "(MISO/PCINT3)PB3_22") (pintype "bidirectional"))
      (node (ref "ICSP") (pin "1") (pinfunction "1_1") (pintype "passive"))
      (node (ref "XIO") (pin "31") (pinfunction "31_31") (pintype "passive"))
    )
    (net (code "53") (name "PB4") (class "Default")
      (node (ref "IC3") (pin "23") (pinfunction "(OC2A/PCINT4)PB4_23") (pintype "bidirectional"))
      (node (ref "JP6") (pin "8") (pinfunction "8_8") (pintype "passive"))
    )
    (net (code "54") (name "PB5") (class "Default")
      (node (ref "IC3") (pin "24") (pinfunction "(OC1A/PCINT5)PB5_24") (pintype "bidirectional"))
      (node (ref "JP6") (pin "7") (pinfunction "7_7") (pintype "passive"))
    )
    (net (code "55") (name "PB6") (class "Default")
      (node (ref "IC3") (pin "25") (pinfunction "(OC1B/PCINT6)PB6_25") (pintype "bidirectional"))
      (node (ref "JP6") (pin "6") (pinfunction "6_6") (pintype "passive"))
    )
    (net (code "56") (name "PB7") (class "Default")
      (node (ref "IC3") (pin "26") (pinfunction "(OC0A/OC1C/PCINT7)PB7_26") (pintype "bidirectional"))
      (node (ref "IC7") (pin "3") (pinfunction "+IN_3") (pintype "input"))
      (node (ref "JP6") (pin "5") (pinfunction "5_5") (pintype "passive"))
    )
    (net (code "57") (name "PC0") (class "Default")
      (node (ref "IC3") (pin "53") (pinfunction "(A8)PC0_53") (pintype "bidirectional"))
      (node (ref "XIO") (pin "18") (pinfunction "18_18") (pintype "passive"))
    )
    (net (code "58") (name "PC1") (class "Default")
      (node (ref "IC3") (pin "54") (pinfunction "(A9)PC1_54") (pintype "bidirectional"))
      (node (ref "XIO") (pin "17") (pinfunction "17_17") (pintype "passive"))
    )
    (net (code "59") (name "PC2") (class "Default")
      (node (ref "IC3") (pin "55") (pinfunction "(A10)PC2_55") (pintype "bidirectional"))
      (node (ref "XIO") (pin "16") (pinfunction "16_16") (pintype "passive"))
    )
    (net (code "60") (name "PC3") (class "Default")
      (node (ref "IC3") (pin "56") (pinfunction "(A11)PC3_56") (pintype "bidirectional"))
      (node (ref "XIO") (pin "15") (pinfunction "15_15") (pintype "passive"))
    )
    (net (code "61") (name "PC4") (class "Default")
      (node (ref "IC3") (pin "57") (pinfunction "(A12)PC4_57") (pintype "bidirectional"))
      (node (ref "XIO") (pin "14") (pinfunction "14_14") (pintype "passive"))
    )
    (net (code "62") (name "PC5") (class "Default")
      (node (ref "IC3") (pin "58") (pinfunction "(A13)PC5_58") (pintype "bidirectional"))
      (node (ref "XIO") (pin "13") (pinfunction "13_13") (pintype "passive"))
    )
    (net (code "63") (name "PC6") (class "Default")
      (node (ref "IC3") (pin "59") (pinfunction "(A14)PC6_59") (pintype "bidirectional"))
      (node (ref "XIO") (pin "12") (pinfunction "12_12") (pintype "passive"))
    )
    (net (code "64") (name "PC7") (class "Default")
      (node (ref "IC3") (pin "60") (pinfunction "(A15)PC7_60") (pintype "bidirectional"))
      (node (ref "XIO") (pin "11") (pinfunction "11_11") (pintype "passive"))
    )
    (net (code "65") (name "PD7") (class "Default")
      (node (ref "IC3") (pin "50") (pinfunction "(T0)PD7_50") (pintype "bidirectional"))
      (node (ref "XIO") (pin "19") (pinfunction "19_19") (pintype "passive"))
    )
    (net (code "66") (name "PE0") (class "Default")
      (node (ref "IC3") (pin "2") (pinfunction "(RXD0/PCIN8)PE0_2") (pintype "bidirectional"))
      (node (ref "PWML") (pin "1") (pinfunction "1_1") (pintype "passive"))
      (node (ref "RN4") (pin "2") (pinfunction "1_2") (pintype "passive"))
    )
    (net (code "67") (name "PE1") (class "Default")
      (node (ref "IC3") (pin "3") (pinfunction "(TXD0)PE1_3") (pintype "bidirectional"))
      (node (ref "PWML") (pin "2") (pinfunction "2_2") (pintype "passive"))
      (node (ref "RN4") (pin "1") (pinfunction "1_1") (pintype "passive"))
    )
    (net (code "68") (name "PE3") (class "Default")
      (node (ref "IC3") (pin "5") (pinfunction "(OC3A/AIN1)PE3_5") (pintype "bidirectional"))
      (node (ref "PWML") (pin "6") (pinfunction "6_6") (pintype "passive"))
    )
    (net (code "69") (name "PE4") (class "Default")
      (node (ref "IC3") (pin "6") (pinfunction "(OC3B/INT4)PE4_6") (pintype "bidirectional"))
      (node (ref "PWML") (pin "3") (pinfunction "3_3") (pintype "passive"))
    )
    (net (code "70") (name "PE5") (class "Default")
      (node (ref "IC3") (pin "7") (pinfunction "(OC3C/INT5)PE5_7") (pintype "bidirectional"))
      (node (ref "PWML") (pin "4") (pinfunction "4_4") (pintype "passive"))
    )
    (net (code "71") (name "PG0") (class "Default")
      (node (ref "IC3") (pin "51") (pinfunction "(WR)PG0_51") (pintype "bidirectional"))
      (node (ref "XIO") (pin "22") (pinfunction "22_22") (pintype "passive"))
    )
    (net (code "72") (name "PG1") (class "Default")
      (node (ref "IC3") (pin "52") (pinfunction "(RD)PG1_52") (pintype "bidirectional"))
      (node (ref "XIO") (pin "21") (pinfunction "21_21") (pintype "passive"))
    )
    (net (code "73") (name "PG2") (class "Default")
      (node (ref "IC3") (pin "70") (pinfunction "(ALE)PG2_70") (pintype "bidirectional"))
      (node (ref "XIO") (pin "20") (pinfunction "20_20") (pintype "passive"))
    )
    (net (code "74") (name "PG5") (class "Default")
      (node (ref "IC3") (pin "1") (pinfunction "(OC0B)PG5_1") (pintype "bidirectional"))
      (node (ref "PWML") (pin "5") (pinfunction "5_5") (pintype "passive"))
    )
    (net (code "75") (name "PH3") (class "Default")
      (node (ref "IC3") (pin "15") (pinfunction "PH3(OC4A)_15") (pintype "bidirectional"))
      (node (ref "PWML") (pin "7") (pinfunction "7_7") (pintype "passive"))
    )
    (net (code "76") (name "PH4") (class "Default")
      (node (ref "IC3") (pin "16") (pinfunction "PH4(OC4B)_16") (pintype "bidirectional"))
      (node (ref "PWML") (pin "8") (pinfunction "8_8") (pintype "passive"))
    )
    (net (code "77") (name "PH5") (class "Default")
      (node (ref "IC3") (pin "17") (pinfunction "PH5(OC4C)_17") (pintype "bidirectional"))
      (node (ref "JP6") (pin "10") (pinfunction "10_10") (pintype "passive"))
    )
    (net (code "78") (name "PH6") (class "Default")
      (node (ref "IC3") (pin "18") (pinfunction "PH6(OC2B)_18") (pintype "bidirectional"))
      (node (ref "JP6") (pin "9") (pinfunction "9_9") (pintype "passive"))
    )
    (net (code "79") (name "PL0") (class "Default")
      (node (ref "IC3") (pin "35") (pinfunction "PL0(ICP4)_35") (pintype "bidirectional"))
      (node (ref "XIO") (pin "30") (pinfunction "30_30") (pintype "passive"))
    )
    (net (code "80") (name "PL1") (class "Default")
      (node (ref "IC3") (pin "36") (pinfunction "PL1(ICP5)_36") (pintype "bidirectional"))
      (node (ref "XIO") (pin "29") (pinfunction "29_29") (pintype "passive"))
    )
    (net (code "81") (name "PL2") (class "Default")
      (node (ref "IC3") (pin "37") (pinfunction "PL2(T5)_37") (pintype "bidirectional"))
      (node (ref "XIO") (pin "28") (pinfunction "28_28") (pintype "passive"))
    )
    (net (code "82") (name "PL3") (class "Default")
      (node (ref "IC3") (pin "38") (pinfunction "PL3(OC5A)_38") (pintype "bidirectional"))
      (node (ref "XIO") (pin "27") (pinfunction "27_27") (pintype "passive"))
    )
    (net (code "83") (name "PL4") (class "Default")
      (node (ref "IC3") (pin "39") (pinfunction "PL4(OC5B)_39") (pintype "bidirectional"))
      (node (ref "XIO") (pin "26") (pinfunction "26_26") (pintype "passive"))
    )
    (net (code "84") (name "PL5") (class "Default")
      (node (ref "IC3") (pin "40") (pinfunction "PL5(OC5C)_40") (pintype "bidirectional"))
      (node (ref "XIO") (pin "25") (pinfunction "25_25") (pintype "passive"))
    )
    (net (code "85") (name "PL6") (class "Default")
      (node (ref "IC3") (pin "41") (pinfunction "PL6_41") (pintype "bidirectional"))
      (node (ref "XIO") (pin "24") (pinfunction "24_24") (pintype "passive"))
    )
    (net (code "86") (name "PL7") (class "Default")
      (node (ref "IC3") (pin "42") (pinfunction "PL7_42") (pintype "bidirectional"))
      (node (ref "XIO") (pin "23") (pinfunction "23_23") (pintype "passive"))
    )
    (net (code "87") (name "PWRIN") (class "Default")
      (node (ref "D1") (pin "A") (pinfunction "A_A") (pintype "passive"))
      (node (ref "X1") (pin "2") (pinfunction "2_2") (pintype "power_in"))
    )
    (net (code "88") (name "RD+") (class "Default")
      (node (ref "IC4") (pin "29") (pinfunction "D+_29") (pintype "bidirectional"))
      (node (ref "RN2") (pin "4") (pinfunction "1_4") (pintype "passive"))
    )
    (net (code "89") (name "RD-") (class "Default")
      (node (ref "IC4") (pin "30") (pinfunction "D-_30") (pintype "bidirectional"))
      (node (ref "RN2") (pin "1") (pinfunction "1_1") (pintype "passive"))
    )
    (net (code "90") (name "RESET") (class "Default")
      (node (ref "C1") (pin "1") (pinfunction "1_1") (pintype "passive"))
      (node (ref "C7") (pin "2") (pinfunction "2_2") (pintype "passive"))
      (node (ref "D3") (pin "A") (pinfunction "A_A") (pintype "passive"))
      (node (ref "IC3") (pin "30") (pinfunction "RESET_30") (pintype "input"))
      (node (ref "ICSP") (pin "5") (pinfunction "5_5") (pintype "passive"))
      (node (ref "POWER") (pin "3") (pinfunction "3_3") (pintype "passive"))
      (node (ref "RESET") (pin "3") (pinfunction "3_3") (pintype "passive"))
      (node (ref "RESET") (pin "4") (pinfunction "4_4") (pintype "passive"))
      (node (ref "RESET-EN") (pin "1") (pinfunction "1_1") (pintype "passive"))
      (node (ref "RESET-EN") (pin "2") (pinfunction "2_2") (pintype "passive"))
      (node (ref "RN5") (pin "1") (pinfunction "1_1") (pintype "passive"))
    )
    (net (code "91") (name "RESET2") (class "Default")
      (node (ref "D2") (pin "A") (pinfunction "A_A") (pintype "passive"))
      (node (ref "IC4") (pin "24") (pinfunction "RESET(PC1/DW)_24") (pintype "input"))
      (node (ref "ICSP1") (pin "5") (pinfunction "5_5") (pintype "passive"))
      (node (ref "RN5") (pin "7") (pinfunction "2_7") (pintype "passive"))
    )
    (net (code "92") (name "RXD1") (class "Default")
      (node (ref "COMMUNICATION") (pin "3") (pinfunction "3_3") (pintype "passive"))
      (node (ref "IC3") (pin "45") (pinfunction "(RXD1/INT2)PD2_45") (pintype "bidirectional"))
    )
    (net (code "93") (name "RXD2") (class "Default")
      (node (ref "COMMUNICATION") (pin "5") (pinfunction "5_5") (pintype "passive"))
      (node (ref "IC3") (pin "12") (pinfunction "PH0(RXD2)_12") (pintype "bidirectional"))
    )
    (net (code "94") (name "RXD3") (class "Default")
      (node (ref "COMMUNICATION") (pin "7") (pinfunction "7_7") (pintype "passive"))
      (node (ref "IC3") (pin "63") (pinfunction "PJ0(RXD3/PCINT9)_63") (pintype "bidirectional"))
    )
    (net (code "95") (name "RXL") (class "Default")
      (node (ref "IC4") (pin "10") (pinfunction "(INT5/AIN3)PD4_10") (pintype "bidirectional"))
      (node (ref "RX") (pin "C") (pinfunction "C_C") (pintype "passive"))
    )
    (net (code "96") (name "SCK2") (class "Default")
      (node (ref "IC4") (pin "15") (pinfunction "(SCLK/PCINT1)PB1_15") (pintype "bidirectional"))
      (node (ref "ICSP1") (pin "3") (pinfunction "3_3") (pintype "passive"))
    )
    (net (code "97") (name "SCL") (class "Default")
      (node (ref "COMMUNICATION") (pin "1") (pinfunction "1_1") (pintype "passive"))
      (node (ref "IC3") (pin "43") (pinfunction "(SCL/INT0)PD0_43") (pintype "bidirectional"))
      (node (ref "JP6") (pin "1") (pinfunction "1_1") (pintype "passive"))
      (node (ref "RN1") (pin "2") (pinfunction "1_2") (pintype "passive"))
    )
    (net (code "98") (name "SDA") (class "Default")
      (node (ref "COMMUNICATION") (pin "2") (pinfunction "2_2") (pintype "passive"))
      (node (ref "IC3") (pin "44") (pinfunction "(SDA/INT1)PD1_44") (pintype "bidirectional"))
      (node (ref "JP6") (pin "2") (pinfunction "2_2") (pintype "passive"))
      (node (ref "RN1") (pin "3") (pinfunction "1_3") (pintype "passive"))
    )
    (net (code "99") (name "TXD1") (class "Default")
      (node (ref "COMMUNICATION") (pin "4") (pinfunction "4_4") (pintype "passive"))
      (node (ref "IC3") (pin "46") (pinfunction "(TXD1/INT3)PD3_46") (pintype "bidirectional"))
    )
    (net (code "100") (name "TXD2") (class "Default")
      (node (ref "COMMUNICATION") (pin "6") (pinfunction "6_6") (pintype "passive"))
      (node (ref "IC3") (pin "13") (pinfunction "PH1(TXD2)_13") (pintype "bidirectional"))
    )
    (net (code "101") (name "TXD3") (class "Default")
      (node (ref "COMMUNICATION") (pin "8") (pinfunction "8_8") (pintype "passive"))
      (node (ref "IC3") (pin "64") (pinfunction "PJ1(TXD3/PCINT10)_64") (pintype "bidirectional"))
    )
    (net (code "102") (name "TXL") (class "Default")
      (node (ref "IC4") (pin "11") (pinfunction "(XCK/AIN4/PCINT12)PD5_11") (pintype "bidirectional"))
      (node (ref "TX") (pin "C") (pinfunction "C_C") (pintype "passive"))
    )
    (net (code "103") (name "UGND") (class "Default")
      (node (ref "C10") (pin "2") (pinfunction "2_2") (pintype "passive"))
      (node (ref "GROUND") (pin "1") (pinfunction "1_1") (pintype "passive"))
      (node (ref "IC4") (pin "28") (pinfunction "UGND_28") (pintype "power_in"))
      (node (ref "L1") (pin "1") (pinfunction "1_1") (pintype "passive"))
      (node (ref "X2") (pin "4") (pinfunction "4_4") (pintype "bidirectional"))
    )
    (net (code "104") (name "USBVCC") (class "Default")
      (node (ref "C8") (pin "1") (pinfunction "1_1") (pintype "passive"))
      (node (ref "F1") (pin "1") (pinfunction "1_1") (pintype "passive"))
      (node (ref "IC4") (pin "31") (pinfunction "UVCC_31") (pintype "power_in"))
      (node (ref "T1") (pin "1") (pinfunction "D_1") (pintype "passive"))
    )
    (net (code "105") (name "USHIELD") (class "Default")
      (node (ref "L1") (pin "2") (pinfunction "2_2") (pintype "passive"))
      (node (ref "X2") (pin "P$1") (pinfunction "P$1_P$1") (pintype "bidirectional"))
      (node (ref "X2") (pin "P$2") (pinfunction "P$2_P$2") (pintype "bidirectional"))
      (node (ref "Z1") (pin "1") (pinfunction "1_1") (pintype "passive"))
      (node (ref "Z2") (pin "1") (pinfunction "1_1") (pintype "passive"))
    )
    (net (code "106") (name "VIN") (class "Default")
      (node (ref "C2") (pin "1") (pinfunction "1_1") (pintype "passive"))
      (node (ref "D1") (pin "C") (pinfunction "C_C") (pintype "passive"))
      (node (ref "IC1") (pin "3") (pinfunction "IN_3") (pintype "input"))
      (node (ref "PC1") (pin "+") (pinfunction "+_+") (pintype "passive"))
      (node (ref "POWER") (pin "8") (pinfunction "8_8") (pintype "passive"))
      (node (ref "RN5") (pin "6") (pinfunction "2_6") (pintype "passive"))
    )
    (net (code "107") (name "VUCAP") (class "Default")
      (node (ref "C10") (pin "1") (pinfunction "1_1") (pintype "passive"))
      (node (ref "IC4") (pin "27") (pinfunction "UCAP_27") (pintype "passive"))
    )
    (net (code "108") (name "XT1") (class "Default")
      (node (ref "C14") (pin "1") (pinfunction "1_1") (pintype "passive"))
      (node (ref "IC4") (pin "1") (pinfunction "XTAL1_1") (pintype "bidirectional"))
      (node (ref "R2") (pin "1") (pinfunction "1_1") (pintype "passive"))
      (node (ref "Y2") (pin "2") (pinfunction "2_2") (pintype "passive"))
    )
    (net (code "109") (name "XT2") (class "Default")
      (node (ref "C15") (pin "1") (pinfunction "1_1") (pintype "passive"))
      (node (ref "IC4") (pin "2") (pinfunction "XTAL2(PC0)_2") (pintype "bidirectional"))
      (node (ref "R2") (pin "2") (pinfunction "2_2") (pintype "passive"))
      (node (ref "Y2") (pin "1") (pinfunction "1_1") (pintype "passive"))
    )
    (net (code "110") (name "XTAL1") (class "Default")
      (node (ref "IC3") (pin "34") (pinfunction "XTAL1_34") (pintype "input"))
      (node (ref "R1") (pin "1") (pinfunction "1_1") (pintype "passive"))
      (node (ref "Y1") (pin "3") (pinfunction "3_3") (pintype "passive"))
    )
    (net (code "111") (name "XTAL2") (class "Default")
      (node (ref "IC3") (pin "33") (pinfunction "XTAL2_33") (pintype "output"))
      (node (ref "R1") (pin "2") (pinfunction "2_2") (pintype "passive"))
      (node (ref "Y1") (pin "1") (pinfunction "1_1") (pintype "passive"))
    )
    (net (code "112") (name "XVCC") (class "Default")
      (node (ref "F1") (pin "2") (pinfunction "2_2") (pintype "passive"))
      (node (ref "X2") (pin "1") (pinfunction "1_1") (pintype "bidirectional"))
    )
    (net (code "113") (name "unconnected-(IC3-(CLKO{slash}ICP3{slash}INT7)PE7-Pad9)") (class "Default")
      (node (ref "IC3") (pin "9") (pinfunction "(CLKO/ICP3/INT7)PE7_9") (pintype "bidirectional"))
    )
    (net (code "114") (name "unconnected-(IC3-(ICP1)PD4-Pad47)") (class "Default")
      (node (ref "IC3") (pin "47") (pinfunction "(ICP1)PD4_47") (pintype "bidirectional"))
    )
    (net (code "115") (name "unconnected-(IC3-(T1)PD6-Pad49)") (class "Default")
      (node (ref "IC3") (pin "49") (pinfunction "(T1)PD6_49") (pintype "bidirectional"))
    )
    (net (code "116") (name "unconnected-(IC3-(T3{slash}INT6)PE6-Pad8)") (class "Default")
      (node (ref "IC3") (pin "8") (pinfunction "(T3/INT6)PE6_8") (pintype "bidirectional"))
    )
    (net (code "117") (name "unconnected-(IC3-(TOSC1)PG4-Pad29)") (class "Default")
      (node (ref "IC3") (pin "29") (pinfunction "(TOSC1)PG4_29") (pintype "bidirectional"))
    )
    (net (code "118") (name "unconnected-(IC3-(TOSC2)PG3-Pad28)") (class "Default")
      (node (ref "IC3") (pin "28") (pinfunction "(TOSC2)PG3_28") (pintype "bidirectional"))
    )
    (net (code "119") (name "unconnected-(IC3-(XCK0{slash}AIN0)PE2-Pad4)") (class "Default")
      (node (ref "IC3") (pin "4") (pinfunction "(XCK0/AIN0)PE2_4") (pintype "bidirectional"))
    )
    (net (code "120") (name "unconnected-(IC3-(XCK1)PD5-Pad48)") (class "Default")
      (node (ref "IC3") (pin "48") (pinfunction "(XCK1)PD5_48") (pintype "bidirectional"))
    )
    (net (code "121") (name "unconnected-(IC3-PH2(XCK2)-Pad14)") (class "Default")
      (node (ref "IC3") (pin "14") (pinfunction "PH2(XCK2)_14") (pintype "bidirectional"))
    )
    (net (code "122") (name "unconnected-(IC3-PH7(T4)-Pad27)") (class "Default")
      (node (ref "IC3") (pin "27") (pinfunction "PH7(T4)_27") (pintype "bidirectional"))
    )
    (net (code "123") (name "unconnected-(IC3-PJ2(XCK3{slash}PCINT11)-Pad65)") (class "Default")
      (node (ref "IC3") (pin "65") (pinfunction "PJ2(XCK3/PCINT11)_65") (pintype "bidirectional"))
    )
    (net (code "124") (name "unconnected-(IC3-PJ3(PCINT12)-Pad66)") (class "Default")
      (node (ref "IC3") (pin "66") (pinfunction "PJ3(PCINT12)_66") (pintype "bidirectional"))
    )
    (net (code "125") (name "unconnected-(IC3-PJ4(PCINT13)-Pad67)") (class "Default")
      (node (ref "IC3") (pin "67") (pinfunction "PJ4(PCINT13)_67") (pintype "bidirectional"))
    )
    (net (code "126") (name "unconnected-(IC3-PJ5(PCINT14)-Pad68)") (class "Default")
      (node (ref "IC3") (pin "68") (pinfunction "PJ5(PCINT14)_68") (pintype "bidirectional"))
    )
    (net (code "127") (name "unconnected-(IC3-PJ6(PCINT15)-Pad69)") (class "Default")
      (node (ref "IC3") (pin "69") (pinfunction "PJ6(PCINT15)_69") (pintype "bidirectional"))
    )
    (net (code "128") (name "unconnected-(IC3-PJ7-Pad79)") (class "Default")
      (node (ref "IC3") (pin "79") (pinfunction "PJ7_79") (pintype "bidirectional"))
    )
    (net (code "129") (name "unconnected-(IC4-(AIN0{slash}INT1)PD1-Pad7)") (class "Default")
      (node (ref "IC4") (pin "7") (pinfunction "(AIN0/INT1)PD1_7") (pintype "bidirectional"))
    )
    (net (code "130") (name "unconnected-(IC4-(AIN2{slash}PCINT11)PC2-Pad5)") (class "Default")
      (node (ref "IC4") (pin "5") (pinfunction "(AIN2/PCINT11)PC2_5") (pintype "bidirectional"))
    )
    (net (code "131") (name "unconnected-(IC4-(INT4{slash}ICP1{slash}CLK0)PC7-Pad22)") (class "Default")
      (node (ref "IC4") (pin "22") (pinfunction "(INT4/ICP1/CLK0)PC7_22") (pintype "bidirectional"))
    )
    (net (code "132") (name "unconnected-(IC4-(OC0B{slash}INT0)PD0-Pad6)") (class "Default")
      (node (ref "IC4") (pin "6") (pinfunction "(OC0B/INT0)PD0_6") (pintype "bidirectional"))
    )
    (net (code "133") (name "unconnected-(IC4-(OC1A{slash}PCINT8)PC6-Pad23)") (class "Default")
      (node (ref "IC4") (pin "23") (pinfunction "(OC1A/PCINT8)PC6_23") (pintype "bidirectional"))
    )
    (net (code "134") (name "unconnected-(IC4-(PCINT9{slash}OC1B)PC5-Pad25)") (class "Default")
      (node (ref "IC4") (pin "25") (pinfunction "(PCINT9/OC1B)PC5_25") (pintype "bidirectional"))
    )
    (net (code "135") (name "unconnected-(IC4-(PCINT10)PC4-Pad26)") (class "Default")
      (node (ref "IC4") (pin "26") (pinfunction "(PCINT10)PC4_26") (pintype "bidirectional"))
    )
    (net (code "136") (name "unconnected-(IC4-(RTS{slash}AIN5{slash}INT6)PD6-Pad12)") (class "Default")
      (node (ref "IC4") (pin "12") (pinfunction "(RTS/AIN5/INT6)PD6_12") (pintype "bidirectional"))
    )
    (net (code "137") (name "unconnected-(IC4-(SS{slash}PCINT0)PB0-Pad14)") (class "Default")
      (node (ref "IC4") (pin "14") (pinfunction "(SS/PCINT0)PB0_14") (pintype "bidirectional"))
    )
    (net (code "138") (name "unconnected-(IC6-NC{slash}FB-Pad4)") (class "Default")
      (node (ref "IC6") (pin "4") (pinfunction "NC/FB_4") (pintype "passive"))
    )
    (net (code "139") (name "unconnected-(POWER-Pad1)") (class "Default")
      (node (ref "POWER") (pin "1") (pinfunction "1_1") (pintype "passive"))
    )
    (net (code "140") (name "unconnected-(RN1-Pad1)") (class "Default")
      (node (ref "RN1") (pin "1") (pinfunction "1_1") (pintype "passive"))
    )
    (net (code "141") (name "unconnected-(RN1A-2-Pad8)") (class "Default")
      (node (ref "RN1") (pin "8") (pinfunction "2_8") (pintype "passive"))
    )
    (net (code "142") (name "unconnected-(RN1D-1-Pad4)") (class "Default")
      (node (ref "RN1") (pin "4") (pinfunction "1_4") (pintype "passive"))
    )
    (net (code "143") (name "unconnected-(RN1D-2-Pad5)") (class "Default")
      (node (ref "RN1") (pin "5") (pinfunction "2_5") (pintype "passive"))
    )
    (net (code "144") (name "unconnected-(RN2B-1-Pad2)") (class "Default")
      (node (ref "RN2") (pin "2") (pinfunction "1_2") (pintype "passive"))
    )
    (net (code "145") (name "unconnected-(RN2B-2-Pad7)") (class "Default")
      (node (ref "RN2") (pin "7") (pinfunction "2_7") (pintype "passive"))
    )
    (net (code "146") (name "unconnected-(RN2C-1-Pad3)") (class "Default")
      (node (ref "RN2") (pin "3") (pinfunction "1_3") (pintype "passive"))
    )
    (net (code "147") (name "unconnected-(RN2C-2-Pad6)") (class "Default")
      (node (ref "RN2") (pin "6") (pinfunction "2_6") (pintype "passive"))
    )
    (net (code "148") (name "unconnected-(RN3C-1-Pad3)") (class "Default")
      (node (ref "RN3") (pin "3") (pinfunction "1_3") (pintype "passive"))
    )
    (net (code "149") (name "unconnected-(RN3C-2-Pad6)") (class "Default")
      (node (ref "RN3") (pin "6") (pinfunction "2_6") (pintype "passive"))
    )
  )
)
